# H-00488_-_Card_Slot.net
KiCad netlist of a schematic drawn in Altium Designer
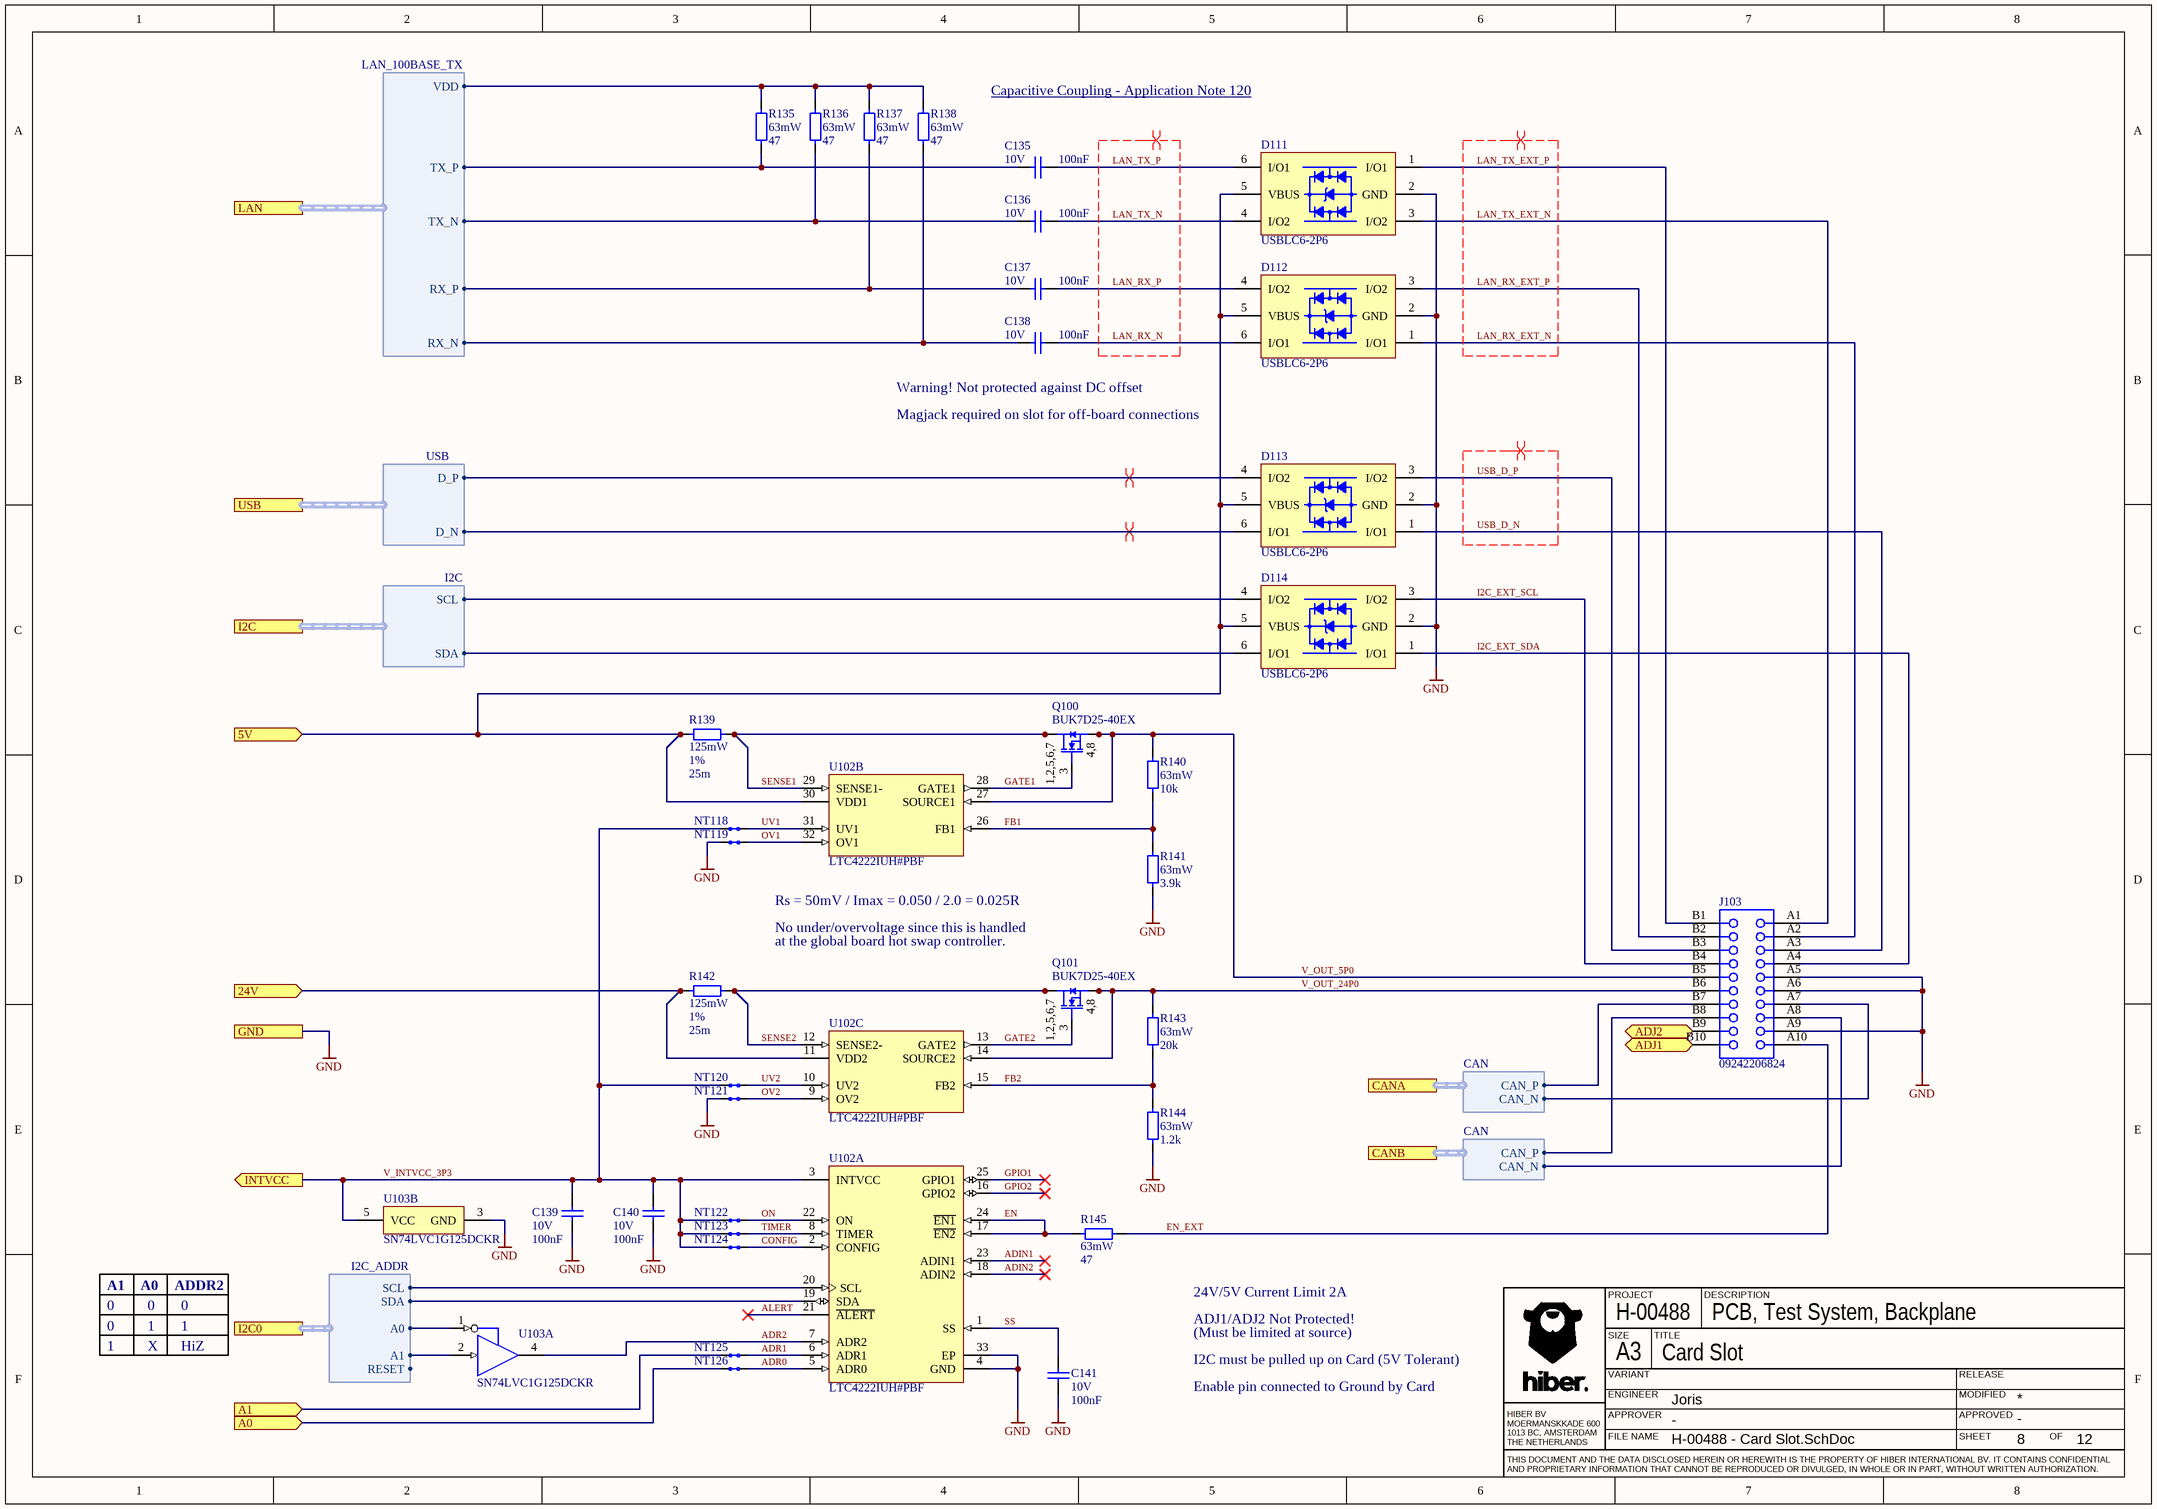
[diagram p0: H-00488 - Card Slot.SchDoc]

(export (version "E")
  (design (tool "Eeschema 10.0.6"))
  (components
    (comp (ref "C135")
      (value "100nF")
      (footprint "CAPC100X50X55L30N")
      (description "CAP Standard 0402 (1005) 100,0nF 10V X7R (Standard)")
      (fields
        (field (name "RATED VOLTAGE") "10V")
        (field (name "TOLERANCE") "10%")
        (field (name "Comment") "C0402C104K8RACTU")
      )
      (libsource (lib "Hiber Vault") (part "CAPACITOR"))
    )
    (comp (ref "C136")
      (value "100nF")
      (footprint "CAPC100X50X55L30N")
      (description "CAP Standard 0402 (1005) 100,0nF 10V X7R (Standard)")
      (fields
        (field (name "RATED VOLTAGE") "10V")
        (field (name "TOLERANCE") "10%")
        (field (name "Comment") "C0402C104K8RACTU")
      )
      (libsource (lib "Hiber Vault") (part "CAPACITOR"))
    )
    (comp (ref "C137")
      (value "100nF")
      (footprint "CAPC100X50X55L30N")
      (description "CAP Standard 0402 (1005) 100,0nF 10V X7R (Standard)")
      (fields
        (field (name "RATED VOLTAGE") "10V")
        (field (name "TOLERANCE") "10%")
        (field (name "Comment") "C0402C104K8RACTU")
      )
      (libsource (lib "Hiber Vault") (part "CAPACITOR"))
    )
    (comp (ref "C138")
      (value "100nF")
      (footprint "CAPC100X50X55L30N")
      (description "CAP Standard 0402 (1005) 100,0nF 10V X7R (Standard)")
      (fields
        (field (name "RATED VOLTAGE") "10V")
        (field (name "TOLERANCE") "10%")
        (field (name "Comment") "C0402C104K8RACTU")
      )
      (libsource (lib "Hiber Vault") (part "CAPACITOR"))
    )
    (comp (ref "C139")
      (value "100nF")
      (footprint "CAPC100X50X55L30N")
      (description "CAP Standard 0402 (1005) 100,0nF 10V X7R (Standard)")
      (fields
        (field (name "RATED VOLTAGE") "10V")
        (field (name "TOLERANCE") "10%")
        (field (name "Comment") "C0402C104K8RACTU")
      )
      (libsource (lib "Hiber Vault") (part "CAPACITOR"))
    )
    (comp (ref "C140")
      (value "100nF")
      (footprint "CAPC100X50X55L30N")
      (description "CAP Standard 0402 (1005) 100,0nF 10V X7R (Standard)")
      (fields
        (field (name "RATED VOLTAGE") "10V")
        (field (name "TOLERANCE") "10%")
        (field (name "Comment") "C0402C104K8RACTU")
      )
      (libsource (lib "Hiber Vault") (part "CAPACITOR"))
    )
    (comp (ref "C141")
      (value "100nF")
      (footprint "CAPC100X50X55L30N")
      (description "CAP Standard 0402 (1005) 100,0nF 10V X7R (Standard)")
      (fields
        (field (name "RATED VOLTAGE") "10V")
        (field (name "TOLERANCE") "10%")
        (field (name "Comment") "C0402C104K8RACTU")
      )
      (libsource (lib "Hiber Vault") (part "CAPACITOR"))
    )
    (comp (ref "D111")
      (value "USBLC6-2P6")
      (footprint "DIOSOFL6P50_160X160X95L29X26")
      (description "TVS DIODE 5.25VWM 17VC SOT666")
      (libsource (lib "") (part "ST_USBLC6-2_1"))
    )
    (comp (ref "D112")
      (value "USBLC6-2P6")
      (footprint "DIOSOFL6P50_160X160X95L29X26")
      (description "TVS DIODE 5.25VWM 17VC SOT666")
      (libsource (lib "Hiber") (part "ST_USBLC6-2"))
    )
    (comp (ref "D113")
      (value "USBLC6-2P6")
      (footprint "DIOSOFL6P50_160X160X95L29X26")
      (description "TVS DIODE 5.25VWM 17VC SOT666")
      (libsource (lib "Hiber") (part "ST_USBLC6-2"))
    )
    (comp (ref "D114")
      (value "USBLC6-2P6")
      (footprint "DIOSOFL6P50_160X160X95L29X26")
      (description "TVS DIODE 5.25VWM 17VC SOT666")
      (libsource (lib "Hiber") (part "ST_USBLC6-2"))
    )
    (comp (ref "J103")
      (value "09242206824")
      (footprint "HARTING_09242206824")
      (description "Board Euro Connector")
      (libsource (lib "Hiber") (part "DIN41612-3B-FEMALE"))
    )
    (comp (ref "NT118")
      (value "NET-TIE")
      (footprint "NT200")
      (description "Net Tie, Inline")
      (libsource (lib "Hiber") (part "NET-TIE"))
    )
    (comp (ref "NT119")
      (value "NET-TIE")
      (footprint "NT200")
      (description "Net Tie, Inline")
      (libsource (lib "Hiber") (part "NET-TIE"))
    )
    (comp (ref "NT120")
      (value "NET-TIE")
      (footprint "NT200")
      (description "Net Tie, Inline")
      (libsource (lib "Hiber") (part "NET-TIE"))
    )
    (comp (ref "NT121")
      (value "NET-TIE")
      (footprint "NT200")
      (description "Net Tie, Inline")
      (libsource (lib "Hiber") (part "NET-TIE"))
    )
    (comp (ref "NT122")
      (value "NET-TIE")
      (footprint "NT200")
      (description "Net Tie, Inline")
      (libsource (lib "Hiber") (part "NET-TIE"))
    )
    (comp (ref "NT123")
      (value "NET-TIE")
      (footprint "NT200")
      (description "Net Tie, Inline")
      (libsource (lib "Hiber") (part "NET-TIE"))
    )
    (comp (ref "NT124")
      (value "NET-TIE")
      (footprint "NT200")
      (description "Net Tie, Inline")
      (libsource (lib "Hiber") (part "NET-TIE"))
    )
    (comp (ref "NT125")
      (value "NET-TIE")
      (footprint "NT200")
      (description "Net Tie, Inline")
      (libsource (lib "Hiber") (part "NET-TIE"))
    )
    (comp (ref "NT126")
      (value "NET-TIE")
      (footprint "NT200")
      (description "Net Tie, Inline")
      (libsource (lib "Hiber") (part "NET-TIE"))
    )
    (comp (ref "Q100")
      (value "BUK7D25-40EX")
      (footprint "NEXPERIA_SOT1220")
      (description "BUK7D25 Series 40V Surface-Mounted N-channel Trench MOSFET - SOT1118")
      (libsource (lib "Hiber") (part "MOSFET-N-8P-SOT1220"))
    )
    (comp (ref "Q101")
      (value "BUK7D25-40EX")
      (footprint "NEXPERIA_SOT1220")
      (description "BUK7D25 Series 40V Surface-Mounted N-channel Trench MOSFET - SOT1118")
      (libsource (lib "Hiber") (part "MOSFET-N-8P-SOT1220"))
    )
    (comp (ref "R135")
      (value "47")
      (footprint "RESC100X50X40L25N")
      (description "RES Standard Thick Film 0402 47R0 ±1% 0,063W")
      (fields
        (field (name "RATED POWER") "63mW")
        (field (name "TOLERANCE") "1%")
        (field (name "Comment") "CRCW040247R0FKED")
      )
      (libsource (lib "Hiber") (part "RESISTOR-2P"))
    )
    (comp (ref "R136")
      (value "47")
      (footprint "RESC100X50X40L25N")
      (description "RES Standard Thick Film 0402 47R0 ±1% 0,063W")
      (fields
        (field (name "RATED POWER") "63mW")
        (field (name "TOLERANCE") "1%")
        (field (name "Comment") "CRCW040247R0FKED")
      )
      (libsource (lib "Hiber") (part "RESISTOR-2P"))
    )
    (comp (ref "R137")
      (value "47")
      (footprint "RESC100X50X40L25N")
      (description "RES Standard Thick Film 0402 47R0 ±1% 0,063W")
      (fields
        (field (name "RATED POWER") "63mW")
        (field (name "TOLERANCE") "1%")
        (field (name "Comment") "CRCW040247R0FKED")
      )
      (libsource (lib "Hiber") (part "RESISTOR-2P"))
    )
    (comp (ref "R138")
      (value "47")
      (footprint "RESC100X50X40L25N")
      (description "RES Standard Thick Film 0402 47R0 ±1% 0,063W")
      (fields
        (field (name "RATED POWER") "63mW")
        (field (name "TOLERANCE") "1%")
        (field (name "Comment") "CRCW040247R0FKED")
      )
      (libsource (lib "Hiber") (part "RESISTOR-2P"))
    )
    (comp (ref "R139")
      (value "25m")
      (footprint "RESC200X125X70L40N")
      (description "RES Power Metal Strip 0805 0R025 ±1% 0,125W")
      (fields
        (field (name "RATED POWER") "125mW")
        (field (name "TOLERANCE") "1%")
        (field (name "Comment") "WSL0805R0250FEA18")
      )
      (libsource (lib "Hiber") (part "RESISTOR-2P"))
    )
    (comp (ref "R140")
      (value "10k")
      (footprint "RESC100X50X40L25N")
      (description "RES Standard Thick Film 0402 10K0 ±1% 0,063W")
      (fields
        (field (name "RATED POWER") "63mW")
        (field (name "TOLERANCE") "1%")
        (field (name "Comment") "CRCW040210K0FKED")
      )
      (libsource (lib "Hiber") (part "RESISTOR-2P"))
    )
    (comp (ref "R141")
      (value "3.9k")
      (footprint "RESC100X50X40L25N")
      (description "RES Standard Thick Film 0402 3K90 ±1% 0,063W")
      (fields
        (field (name "RATED POWER") "63mW")
        (field (name "TOLERANCE") "1%")
        (field (name "Comment") "CRCW04023K90FKED")
      )
      (libsource (lib "Hiber") (part "RESISTOR-2P"))
    )
    (comp (ref "R142")
      (value "25m")
      (footprint "RESC200X125X70L40N")
      (description "RES Power Metal Strip 0805 0R025 ±1% 0,125W")
      (fields
        (field (name "RATED POWER") "125mW")
        (field (name "TOLERANCE") "1%")
        (field (name "Comment") "WSL0805R0250FEA18")
      )
      (libsource (lib "Hiber") (part "RESISTOR-2P"))
    )
    (comp (ref "R143")
      (value "20k")
      (footprint "RESC100X50X40L25N")
      (description "RES Standard Thick Film 0402 20K0 ±1% 0,063W")
      (fields
        (field (name "RATED POWER") "63mW")
        (field (name "TOLERANCE") "1%")
        (field (name "Comment") "CRCW040220K0FKED")
      )
      (libsource (lib "Hiber") (part "RESISTOR-2P"))
    )
    (comp (ref "R144")
      (value "1.2k")
      (footprint "RESC100X50X40L25N")
      (description "RES Standard Thick Film 0402 1K20 ±1% 0,063W")
      (fields
        (field (name "RATED POWER") "63mW")
        (field (name "TOLERANCE") "1%")
        (field (name "Comment") "CRCW04021K20FKED")
      )
      (libsource (lib "Hiber") (part "RESISTOR-2P"))
    )
    (comp (ref "R145")
      (value "47")
      (footprint "RESC100X50X40L25N")
      (description "RES Standard Thick Film 0402 47R0 ±1% 0,063W")
      (fields
        (field (name "RATED POWER") "63mW")
        (field (name "TOLERANCE") "1%")
        (field (name "Comment") "CRCW040247R0FKED")
      )
      (libsource (lib "Hiber") (part "RESISTOR-2P"))
    )
    (comp (ref "U102")
      (value "LTC4222IUH#PBF")
      (footprint "QFN33P50_500X500X80L40X25T345")
      (description "Power Supply Support Circuit, Adjustable, 2 Channel, CMOS, PQCC32")
      (libsource (lib "Hiber") (part "LT-LTC4222-UH-32"))
    )
    (comp (ref "U103")
      (value "SN74LVC1G125DCKR")
      (footprint "SOT23-5P65_210X110L36X22")
      (description "Bus Driver, LVC/LCX/Z Series, 1-Func, 1-Bit, True Output, CMOS, PDSO5")
      (libsource (lib "Hiber") (part "TI-SN74AXXXX1X125-5"))
    )
  )
  (nets
    (net (code "6") (name "/5V") (class "Default")
      (node (ref "D111") (pin "5") (pinfunction "VBUS_5") (pintype "passive"))
      (node (ref "D112") (pin "5") (pinfunction "VBUS_5") (pintype "passive"))
      (node (ref "D113") (pin "5") (pinfunction "VBUS_5") (pintype "passive"))
      (node (ref "D114") (pin "5") (pinfunction "VBUS_5") (pintype "passive"))
      (node (ref "R139") (pin "2") (pinfunction "2_2") (pintype "passive"))
      (node (ref "U102") (pin "30") (pinfunction "VDD1_30") (pintype "power_in"))
    )
    (net (code "7") (name "/24V") (class "Default")
      (node (ref "R142") (pin "2") (pinfunction "2_2") (pintype "passive"))
      (node (ref "U102") (pin "11") (pinfunction "VDD2_11") (pintype "power_in"))
    )
    (net (code "8") (name "/A0") (class "Default")
      (node (ref "NT126") (pin "1") (pinfunction "1_1") (pintype "passive"))
    )
    (net (code "9") (name "/A1") (class "Default")
      (node (ref "NT125") (pin "1") (pinfunction "1_1") (pintype "passive"))
    )
    (net (code "10") (name "/ADIN1") (class "Default")
      (node (ref "U102") (pin "23") (pinfunction "ADIN1_23") (pintype "input+no_connect"))
    )
    (net (code "11") (name "/ADIN2") (class "Default")
      (node (ref "U102") (pin "18") (pinfunction "ADIN2_18") (pintype "input+no_connect"))
    )
    (net (code "12") (name "/ADJ1") (class "Default")
      (node (ref "J103") (pin "B10") (pinfunction "B10_B10") (pintype "passive"))
    )
    (net (code "13") (name "/ADJ2") (class "Default")
      (node (ref "J103") (pin "B9") (pinfunction "B9_B9") (pintype "passive"))
    )
    (net (code "14") (name "/ADR0") (class "Default")
      (node (ref "NT126") (pin "2") (pinfunction "1_2") (pintype "passive"))
      (node (ref "U102") (pin "5") (pinfunction "ADR0_5") (pintype "input"))
    )
    (net (code "15") (name "/ADR1") (class "Default")
      (node (ref "NT125") (pin "2") (pinfunction "1_2") (pintype "passive"))
      (node (ref "U102") (pin "6") (pinfunction "ADR1_6") (pintype "input"))
    )
    (net (code "16") (name "/ADR2") (class "Default")
      (node (ref "U102") (pin "7") (pinfunction "ADR2_7") (pintype "input"))
      (node (ref "U103") (pin "4") (pinfunction "Y_4") (pintype "tri_state"))
    )
    (net (code "17") (name "/ALERT") (class "Default")
      (node (ref "U102") (pin "21") (pinfunction "~{ALERT}_21") (pintype "open_collector+no_connect"))
    )
    (net (code "18") (name "/CONFIG") (class "Default")
      (node (ref "NT124") (pin "2") (pinfunction "1_2") (pintype "passive"))
      (node (ref "U102") (pin "2") (pinfunction "CONFIG_2") (pintype "input"))
    )
    (net (code "19") (name "/D_N") (class "Default")
      (node (ref "D113") (pin "6") (pinfunction "I/O1_6") (pintype "passive"))
    )
    (net (code "20") (name "/D_P") (class "Default")
      (node (ref "D113") (pin "4") (pinfunction "I/O2_4") (pintype "passive"))
    )
    (net (code "21") (name "/EN") (class "Default")
      (node (ref "R145") (pin "1") (pinfunction "1_1") (pintype "passive"))
      (node (ref "U102") (pin "17") (pinfunction "~{EN2}_17") (pintype "input"))
      (node (ref "U102") (pin "24") (pinfunction "~{EN1}_24") (pintype "input"))
    )
    (net (code "22") (name "/EN_EXT") (class "Default")
      (node (ref "J103") (pin "A10") (pinfunction "A10_A10") (pintype "passive"))
      (node (ref "R145") (pin "2") (pinfunction "2_2") (pintype "passive"))
    )
    (net (code "23") (name "/FB1") (class "Default")
      (node (ref "R140") (pin "2") (pinfunction "2_2") (pintype "passive"))
      (node (ref "R141") (pin "1") (pinfunction "1_1") (pintype "passive"))
      (node (ref "U102") (pin "26") (pinfunction "FB1_26") (pintype "input"))
    )
    (net (code "24") (name "/FB2") (class "Default")
      (node (ref "R143") (pin "2") (pinfunction "2_2") (pintype "passive"))
      (node (ref "R144") (pin "1") (pinfunction "1_1") (pintype "passive"))
      (node (ref "U102") (pin "15") (pinfunction "FB2_15") (pintype "input"))
    )
    (net (code "25") (name "/GATE1") (class "Default")
      (node (ref "Q100") (pin "3") (pinfunction "G_3") (pintype "passive"))
      (node (ref "U102") (pin "28") (pinfunction "GATE1_28") (pintype "output"))
    )
    (net (code "26") (name "/GATE2") (class "Default")
      (node (ref "Q101") (pin "3") (pinfunction "G_3") (pintype "passive"))
      (node (ref "U102") (pin "13") (pinfunction "GATE2_13") (pintype "output"))
    )
    (net (code "27") (name "/GPIO1") (class "Default")
      (node (ref "U102") (pin "25") (pinfunction "GPIO1_25") (pintype "bidirectional+no_connect"))
    )
    (net (code "28") (name "/GPIO2") (class "Default")
      (node (ref "U102") (pin "16") (pinfunction "GPIO2_16") (pintype "bidirectional+no_connect"))
    )
    (net (code "29") (name "/I2C_EXT_SCL") (class "Default")
      (node (ref "D114") (pin "3") (pinfunction "I/O2_3") (pintype "passive"))
      (node (ref "J103") (pin "B4") (pinfunction "B4_B4") (pintype "passive"))
    )
    (net (code "30") (name "/I2C_EXT_SDA") (class "Default")
      (node (ref "D114") (pin "1") (pinfunction "I/O1_1") (pintype "passive"))
      (node (ref "J103") (pin "A4") (pinfunction "A4_A4") (pintype "passive"))
    )
    (net (code "31") (name "/LAN_RX_EXT_N") (class "Default")
      (node (ref "D112") (pin "1") (pinfunction "I/O1_1") (pintype "passive"))
      (node (ref "J103") (pin "A2") (pinfunction "A2_A2") (pintype "passive"))
    )
    (net (code "32") (name "/LAN_RX_EXT_P") (class "Default")
      (node (ref "D112") (pin "3") (pinfunction "I/O2_3") (pintype "passive"))
      (node (ref "J103") (pin "B2") (pinfunction "B2_B2") (pintype "passive"))
    )
    (net (code "33") (name "/LAN_RX_N") (class "Default")
      (node (ref "C138") (pin "2") (pinfunction "2_2") (pintype "passive"))
      (node (ref "D112") (pin "6") (pinfunction "I/O1_6") (pintype "passive"))
    )
    (net (code "34") (name "/LAN_RX_P") (class "Default")
      (node (ref "C137") (pin "2") (pinfunction "2_2") (pintype "passive"))
      (node (ref "D112") (pin "4") (pinfunction "I/O2_4") (pintype "passive"))
    )
    (net (code "35") (name "/LAN_TX_EXT_N") (class "Default")
      (node (ref "D111") (pin "3") (pinfunction "I/O2_3") (pintype "passive"))
      (node (ref "J103") (pin "A1") (pinfunction "A1_A1") (pintype "passive"))
    )
    (net (code "36") (name "/LAN_TX_EXT_P") (class "Default")
      (node (ref "D111") (pin "1") (pinfunction "I/O1_1") (pintype "passive"))
      (node (ref "J103") (pin "B1") (pinfunction "B1_B1") (pintype "passive"))
    )
    (net (code "37") (name "/LAN_TX_N") (class "Default")
      (node (ref "C136") (pin "2") (pinfunction "2_2") (pintype "passive"))
      (node (ref "D111") (pin "4") (pinfunction "I/O2_4") (pintype "passive"))
    )
    (net (code "38") (name "/LAN_TX_P") (class "Default")
      (node (ref "C135") (pin "2") (pinfunction "2_2") (pintype "passive"))
      (node (ref "D111") (pin "6") (pinfunction "I/O1_6") (pintype "passive"))
    )
    (net (code "39") (name "/ON") (class "Default")
      (node (ref "NT122") (pin "2") (pinfunction "1_2") (pintype "passive"))
      (node (ref "U102") (pin "22") (pinfunction "ON_22") (pintype "input"))
    )
    (net (code "40") (name "/OV1") (class "Default")
      (node (ref "NT119") (pin "2") (pinfunction "1_2") (pintype "passive"))
      (node (ref "U102") (pin "32") (pinfunction "OV1_32") (pintype "input"))
    )
    (net (code "41") (name "/OV2") (class "Default")
      (node (ref "NT121") (pin "2") (pinfunction "1_2") (pintype "passive"))
      (node (ref "U102") (pin "9") (pinfunction "OV2_9") (pintype "input"))
    )
    (net (code "42") (name "/RX_N") (class "Default")
      (node (ref "C138") (pin "1") (pinfunction "1_1") (pintype "passive"))
      (node (ref "R138") (pin "1") (pinfunction "1_1") (pintype "passive"))
    )
    (net (code "43") (name "/RX_P") (class "Default")
      (node (ref "C137") (pin "1") (pinfunction "1_1") (pintype "passive"))
      (node (ref "R137") (pin "1") (pinfunction "1_1") (pintype "passive"))
    )
    (net (code "44") (name "/SENSE1") (class "Default")
      (node (ref "Q100") (pin "1") (pinfunction "D_1") (pintype "passive"))
      (node (ref "Q100") (pin "2") (pinfunction "D_2") (pintype "passive"))
      (node (ref "Q100") (pin "5") (pinfunction "D_5") (pintype "passive"))
      (node (ref "Q100") (pin "6") (pinfunction "D_6") (pintype "passive"))
      (node (ref "Q100") (pin "7") (pinfunction "D_7") (pintype "passive"))
      (node (ref "R139") (pin "1") (pinfunction "1_1") (pintype "passive"))
      (node (ref "U102") (pin "29") (pinfunction "SENSE1-_29") (pintype "input"))
    )
    (net (code "45") (name "/SENSE2") (class "Default")
      (node (ref "Q101") (pin "1") (pinfunction "D_1") (pintype "passive"))
      (node (ref "Q101") (pin "2") (pinfunction "D_2") (pintype "passive"))
      (node (ref "Q101") (pin "5") (pinfunction "D_5") (pintype "passive"))
      (node (ref "Q101") (pin "6") (pinfunction "D_6") (pintype "passive"))
      (node (ref "Q101") (pin "7") (pinfunction "D_7") (pintype "passive"))
      (node (ref "R142") (pin "1") (pinfunction "1_1") (pintype "passive"))
      (node (ref "U102") (pin "12") (pinfunction "SENSE2-_12") (pintype "input"))
    )
    (net (code "46") (name "/SS") (class "Default")
      (node (ref "C141") (pin "1") (pinfunction "1_1") (pintype "passive"))
      (node (ref "U102") (pin "1") (pinfunction "SS_1") (pintype "input"))
    )
    (net (code "47") (name "/TIMER") (class "Default")
      (node (ref "NT123") (pin "2") (pinfunction "1_2") (pintype "passive"))
      (node (ref "U102") (pin "8") (pinfunction "TIMER_8") (pintype "input"))
    )
    (net (code "48") (name "/TX_N") (class "Default")
      (node (ref "C136") (pin "1") (pinfunction "1_1") (pintype "passive"))
      (node (ref "R136") (pin "1") (pinfunction "1_1") (pintype "passive"))
    )
    (net (code "49") (name "/TX_P") (class "Default")
      (node (ref "C135") (pin "1") (pinfunction "1_1") (pintype "passive"))
      (node (ref "R135") (pin "1") (pinfunction "1_1") (pintype "passive"))
    )
    (net (code "50") (name "/USB_D_N") (class "Default")
      (node (ref "D113") (pin "1") (pinfunction "I/O1_1") (pintype "passive"))
      (node (ref "J103") (pin "A3") (pinfunction "A3_A3") (pintype "passive"))
    )
    (net (code "51") (name "/USB_D_P") (class "Default")
      (node (ref "D113") (pin "3") (pinfunction "I/O2_3") (pintype "passive"))
      (node (ref "J103") (pin "B3") (pinfunction "B3_B3") (pintype "passive"))
    )
    (net (code "52") (name "/UV1") (class "Default")
      (node (ref "NT118") (pin "2") (pinfunction "1_2") (pintype "passive"))
      (node (ref "U102") (pin "31") (pinfunction "UV1_31") (pintype "input"))
    )
    (net (code "53") (name "/UV2") (class "Default")
      (node (ref "NT120") (pin "2") (pinfunction "1_2") (pintype "passive"))
      (node (ref "U102") (pin "10") (pinfunction "UV2_10") (pintype "input"))
    )
    (net (code "54") (name "/VDD") (class "Default")
      (node (ref "R135") (pin "2") (pinfunction "2_2") (pintype "passive"))
      (node (ref "R136") (pin "2") (pinfunction "2_2") (pintype "passive"))
      (node (ref "R137") (pin "2") (pinfunction "2_2") (pintype "passive"))
      (node (ref "R138") (pin "2") (pinfunction "2_2") (pintype "passive"))
    )
    (net (code "55") (name "/V_INTVCC_3P3") (class "Default")
      (node (ref "C139") (pin "1") (pinfunction "1_1") (pintype "passive"))
      (node (ref "C140") (pin "1") (pinfunction "1_1") (pintype "passive"))
      (node (ref "NT118") (pin "1") (pinfunction "1_1") (pintype "passive"))
      (node (ref "NT120") (pin "1") (pinfunction "1_1") (pintype "passive"))
      (node (ref "NT122") (pin "1") (pinfunction "1_1") (pintype "passive"))
      (node (ref "NT123") (pin "1") (pinfunction "1_1") (pintype "passive"))
      (node (ref "NT124") (pin "1") (pinfunction "1_1") (pintype "passive"))
      (node (ref "U102") (pin "3") (pinfunction "INTVCC_3") (pintype "power_in"))
      (node (ref "U103") (pin "5") (pinfunction "VCC_5") (pintype "power_in"))
    )
    (net (code "56") (name "/V_OUT_5P0") (class "Default")
      (node (ref "J103") (pin "B5") (pinfunction "B5_B5") (pintype "passive"))
      (node (ref "Q100") (pin "4") (pinfunction "S_4") (pintype "passive"))
      (node (ref "Q100") (pin "8") (pinfunction "S_8") (pintype "passive"))
      (node (ref "R140") (pin "1") (pinfunction "1_1") (pintype "passive"))
      (node (ref "U102") (pin "27") (pinfunction "SOURCE1_27") (pintype "input"))
    )
    (net (code "57") (name "/V_OUT_24P0") (class "Default")
      (node (ref "J103") (pin "B6") (pinfunction "B6_B6") (pintype "passive"))
      (node (ref "Q101") (pin "4") (pinfunction "S_4") (pintype "passive"))
      (node (ref "Q101") (pin "8") (pinfunction "S_8") (pintype "passive"))
      (node (ref "R143") (pin "1") (pinfunction "1_1") (pintype "passive"))
      (node (ref "U102") (pin "14") (pinfunction "SOURCE2_14") (pintype "input"))
    )
    (net (code "63") (name "GND") (class "Default")
      (node (ref "C139") (pin "2") (pinfunction "2_2") (pintype "passive"))
      (node (ref "C140") (pin "2") (pinfunction "2_2") (pintype "passive"))
      (node (ref "C141") (pin "2") (pinfunction "2_2") (pintype "passive"))
      (node (ref "D111") (pin "2") (pinfunction "GND_2") (pintype "passive"))
      (node (ref "D112") (pin "2") (pinfunction "GND_2") (pintype "passive"))
      (node (ref "D113") (pin "2") (pinfunction "GND_2") (pintype "passive"))
      (node (ref "D114") (pin "2") (pinfunction "GND_2") (pintype "passive"))
      (node (ref "J103") (pin "A5") (pinfunction "A5_A5") (pintype "passive"))
      (node (ref "J103") (pin "A6") (pinfunction "A6_A6") (pintype "passive"))
      (node (ref "J103") (pin "A9") (pinfunction "A9_A9") (pintype "passive"))
      (node (ref "NT119") (pin "1") (pinfunction "1_1") (pintype "passive"))
      (node (ref "NT121") (pin "1") (pinfunction "1_1") (pintype "passive"))
      (node (ref "R141") (pin "2") (pinfunction "2_2") (pintype "passive"))
      (node (ref "R144") (pin "2") (pinfunction "2_2") (pintype "passive"))
      (node (ref "U102") (pin "33") (pinfunction "EP_33") (pintype "power_in"))
      (node (ref "U102") (pin "4") (pinfunction "GND_4") (pintype "power_in"))
      (node (ref "U103") (pin "3") (pinfunction "GND_3") (pintype "power_in"))
    )
    (net (code "64") (name "unconnected-(D114-I{slash}O1-Pad6)") (class "Default")
      (node (ref "D114") (pin "6") (pinfunction "I/O1_6") (pintype "passive"))
    )
    (net (code "65") (name "unconnected-(D114-I{slash}O2-Pad4)") (class "Default")
      (node (ref "D114") (pin "4") (pinfunction "I/O2_4") (pintype "passive"))
    )
    (net (code "66") (name "unconnected-(J103-PadA7)") (class "Default")
      (node (ref "J103") (pin "A7") (pinfunction "A7_A7") (pintype "passive"))
    )
    (net (code "67") (name "unconnected-(J103-PadA8)") (class "Default")
      (node (ref "J103") (pin "A8") (pinfunction "A8_A8") (pintype "passive"))
    )
    (net (code "68") (name "unconnected-(J103-PadB7)") (class "Default")
      (node (ref "J103") (pin "B7") (pinfunction "B7_B7") (pintype "passive"))
    )
    (net (code "69") (name "unconnected-(J103-PadB8)") (class "Default")
      (node (ref "J103") (pin "B8") (pinfunction "B8_B8") (pintype "passive"))
    )
    (net (code "70") (name "unconnected-(U102A-SCL-Pad20)") (class "Default")
      (node (ref "U102") (pin "20") (pinfunction "SCL_20") (pintype "input"))
    )
    (net (code "71") (name "unconnected-(U102A-SDA-Pad19)") (class "Default")
      (node (ref "U102") (pin "19") (pinfunction "SDA_19") (pintype "bidirectional"))
    )
    (net (code "72") (name "unconnected-(U103A-A-Pad2)") (class "Default")
      (node (ref "U103") (pin "2") (pinfunction "A_2") (pintype "input"))
    )
    (net (code "73") (name "unconnected-(U103A-~{OE}-Pad1)") (class "Default")
      (node (ref "U103") (pin "1") (pinfunction "~{OE}_1") (pintype "input"))
    )
  )
)
